# sGPSDO_MCU_1V0.net
KiCad netlist of a schematic drawn in EAGLE
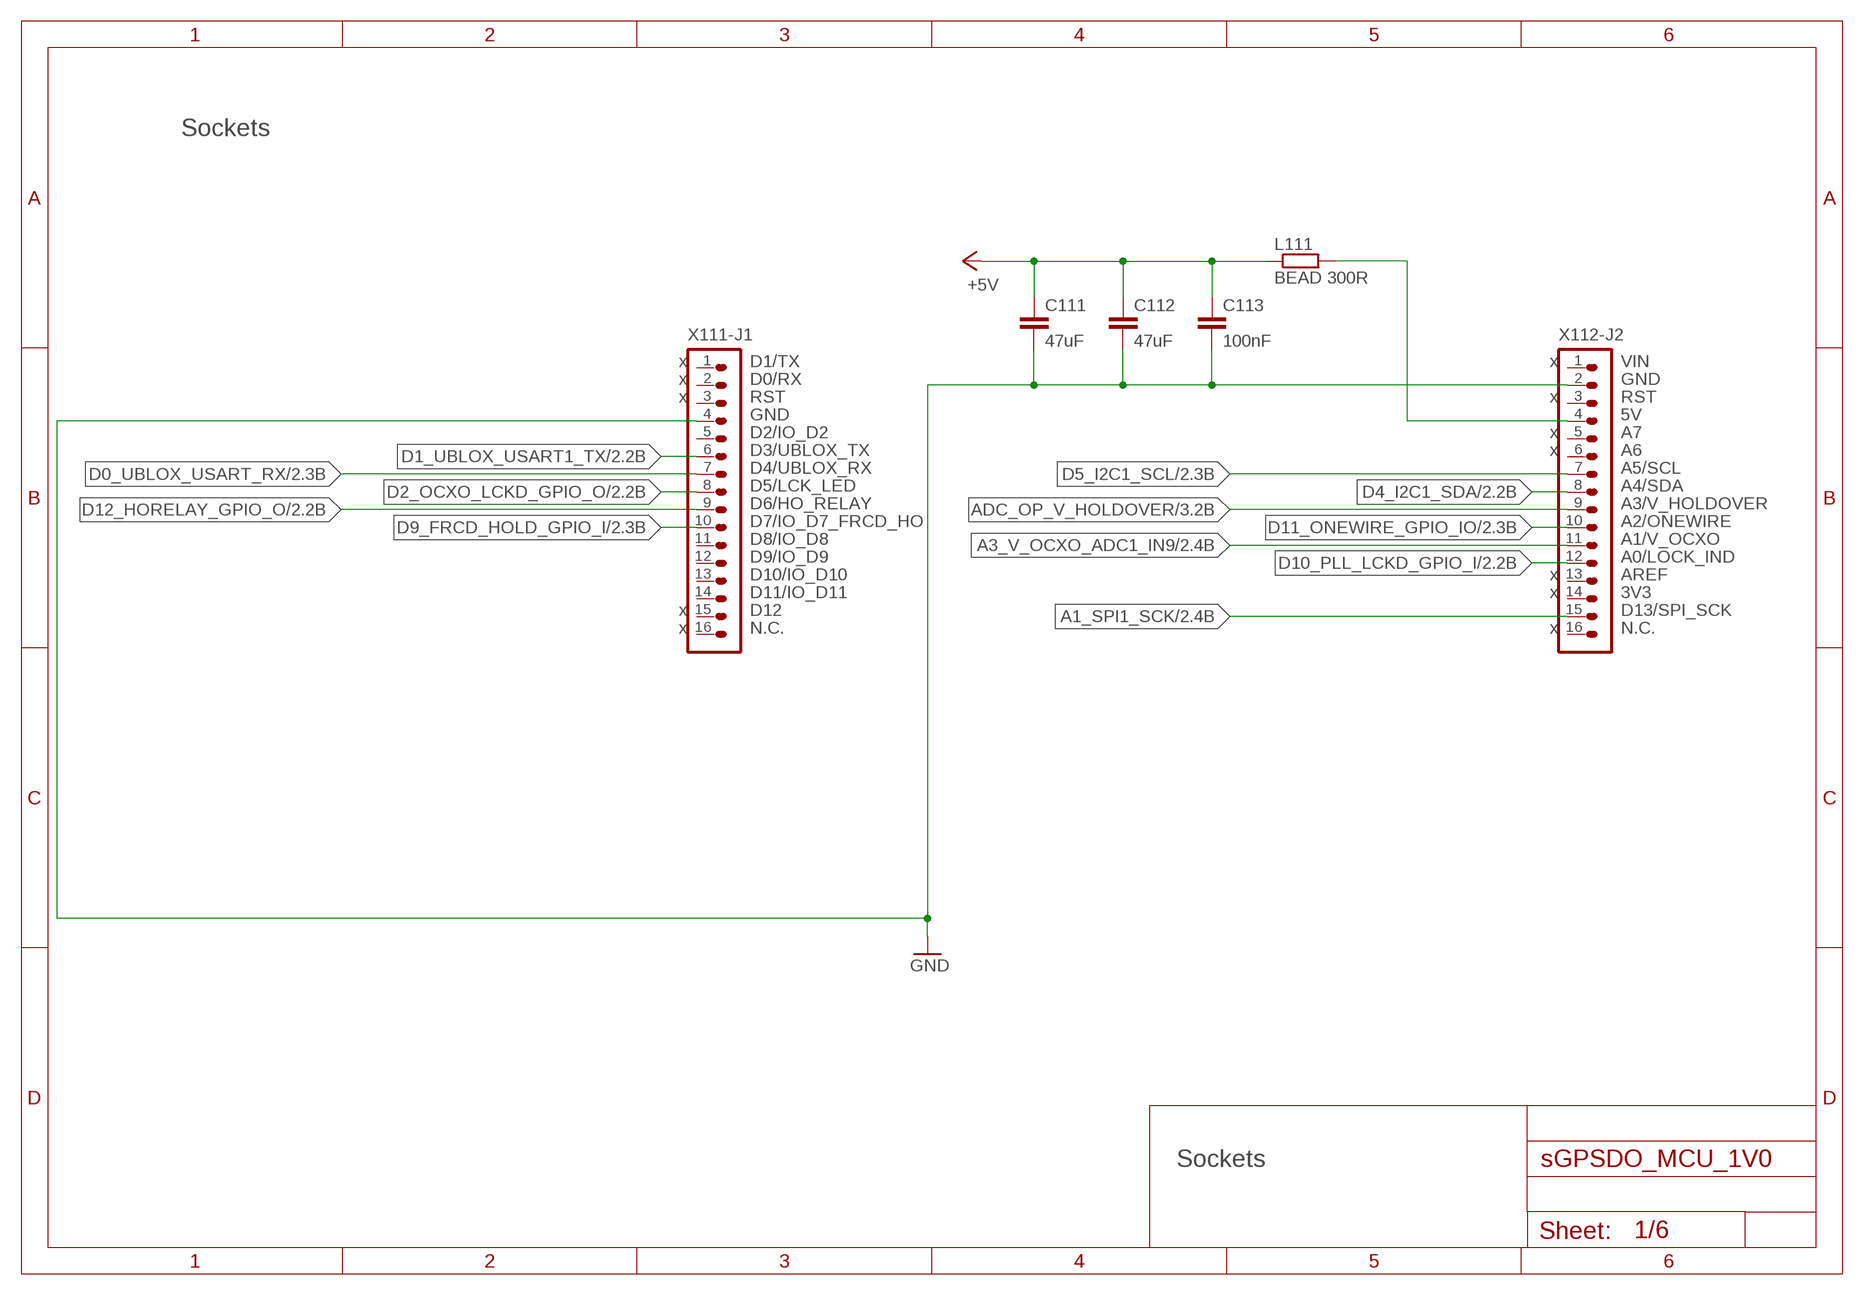
[diagram p0: schematic, sheet 1]
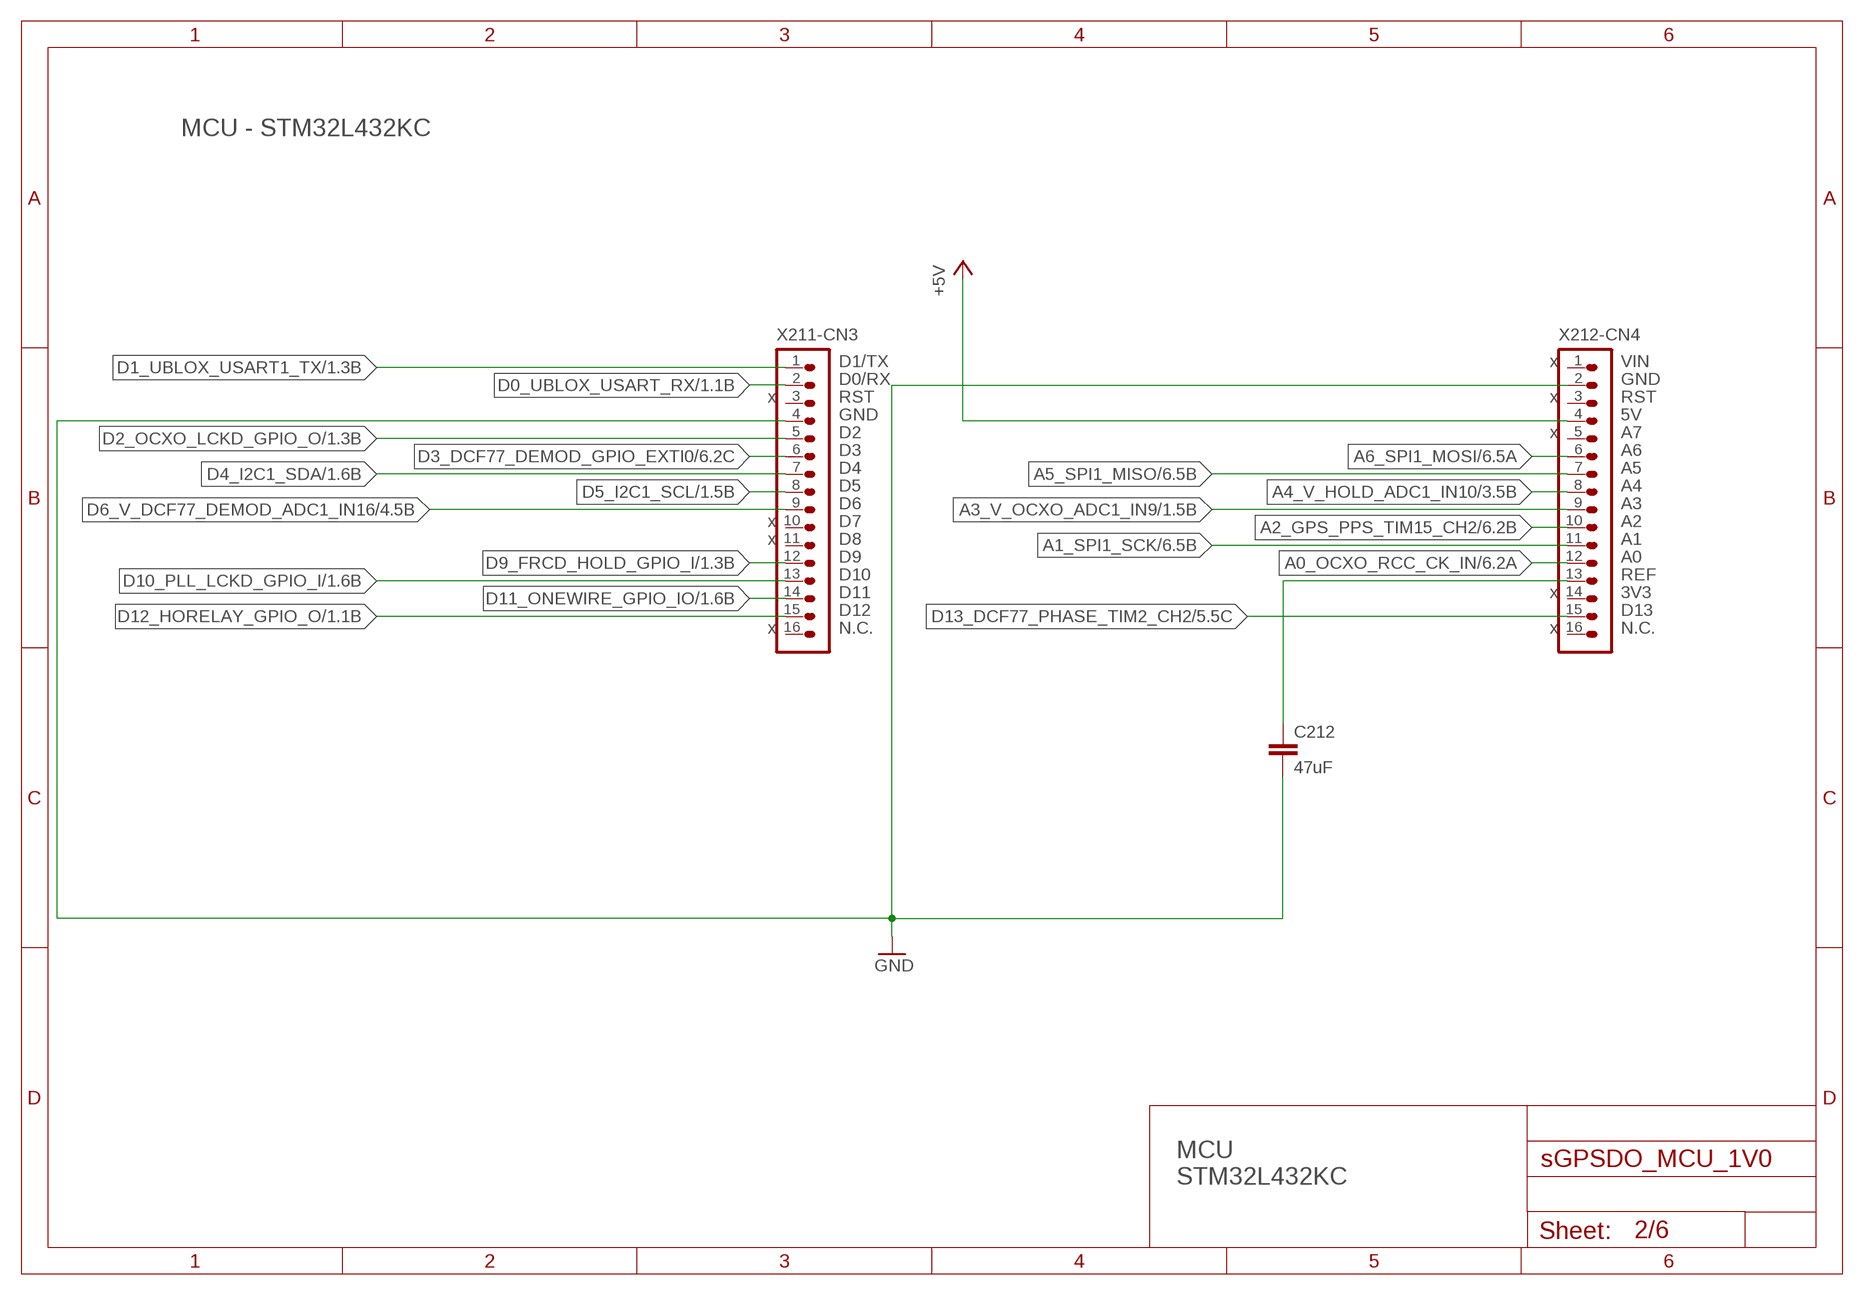
[diagram p1: schematic, sheet 2]
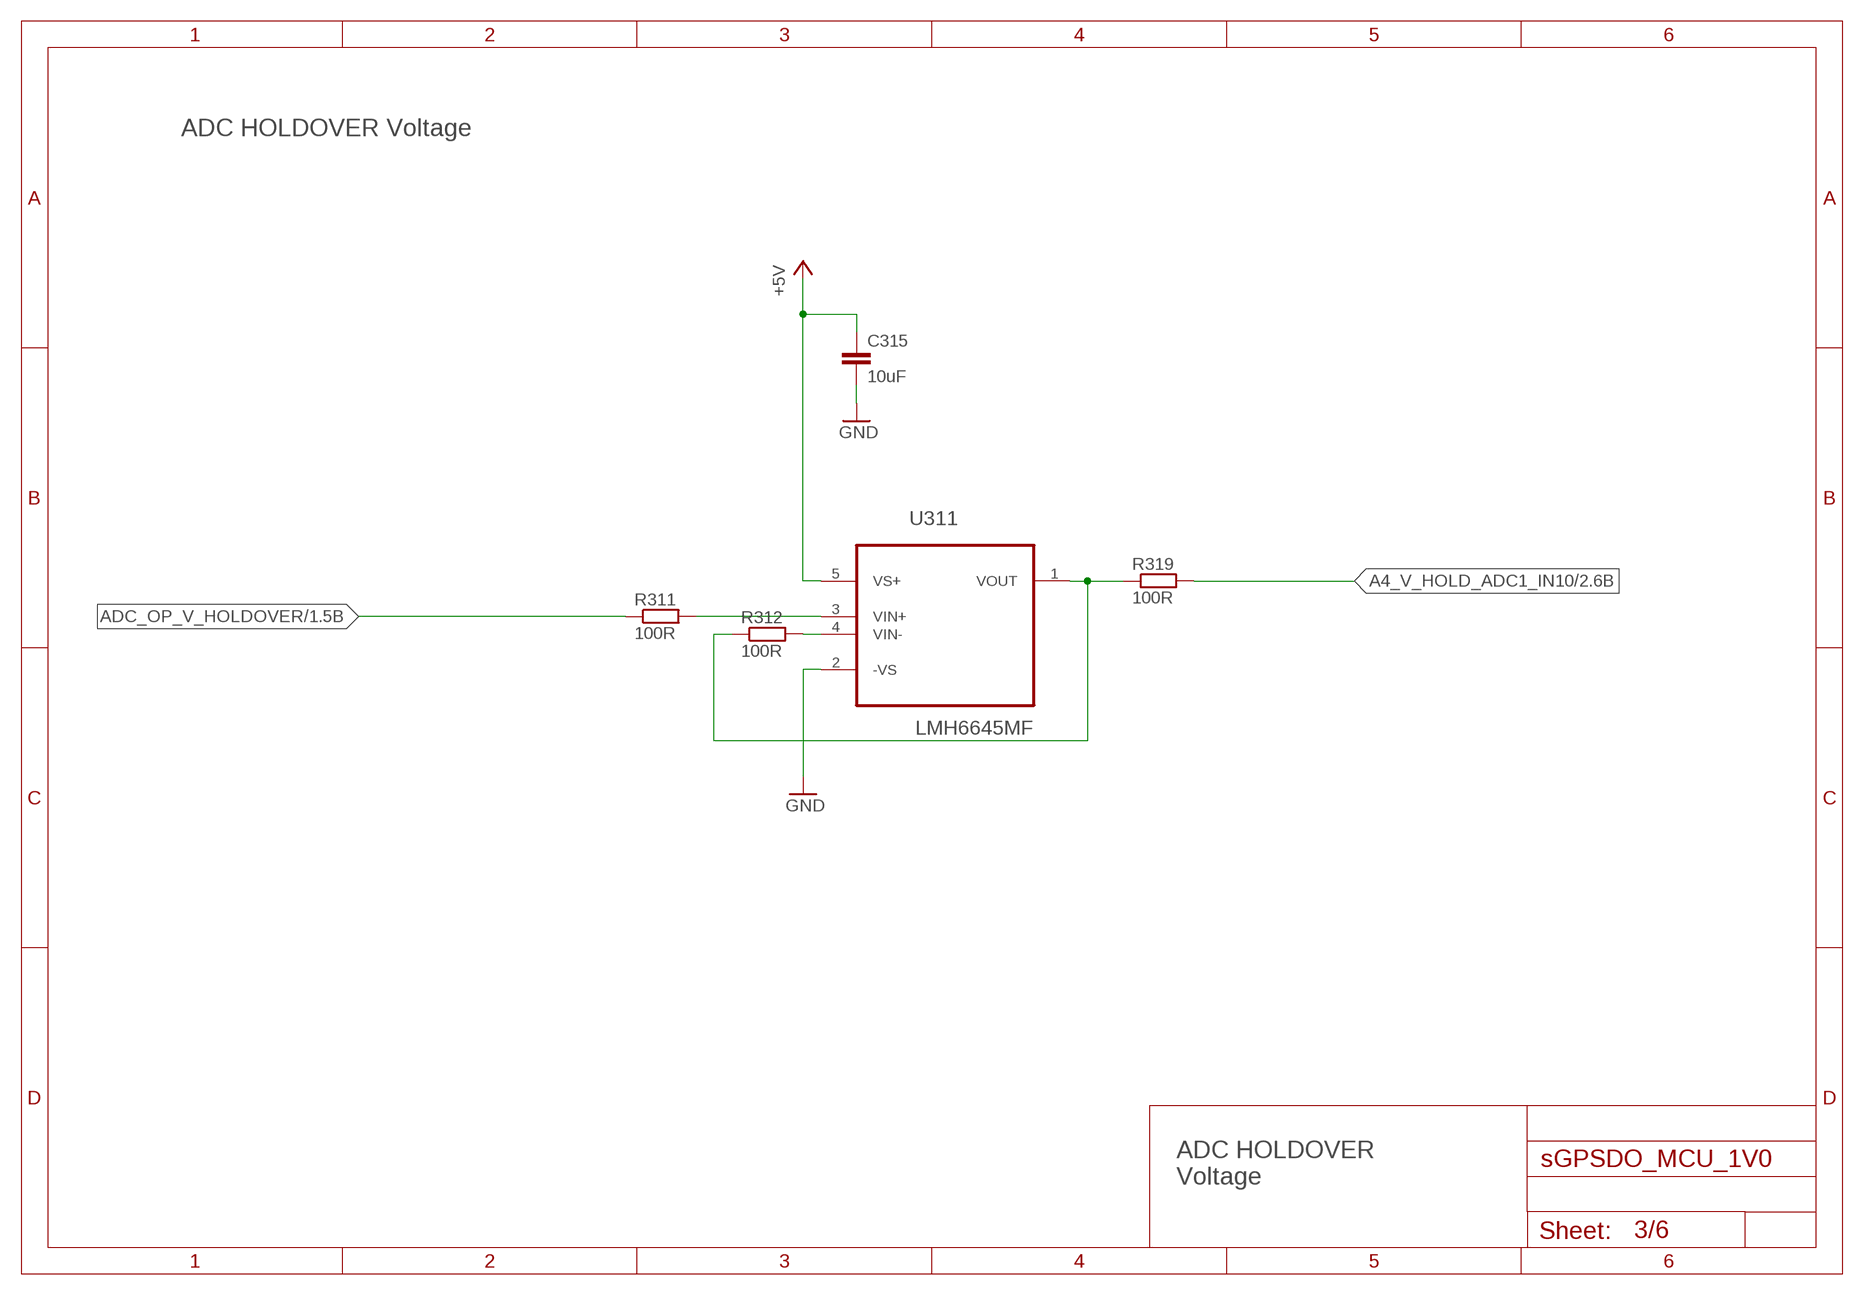
[diagram p2: schematic, sheet 3]
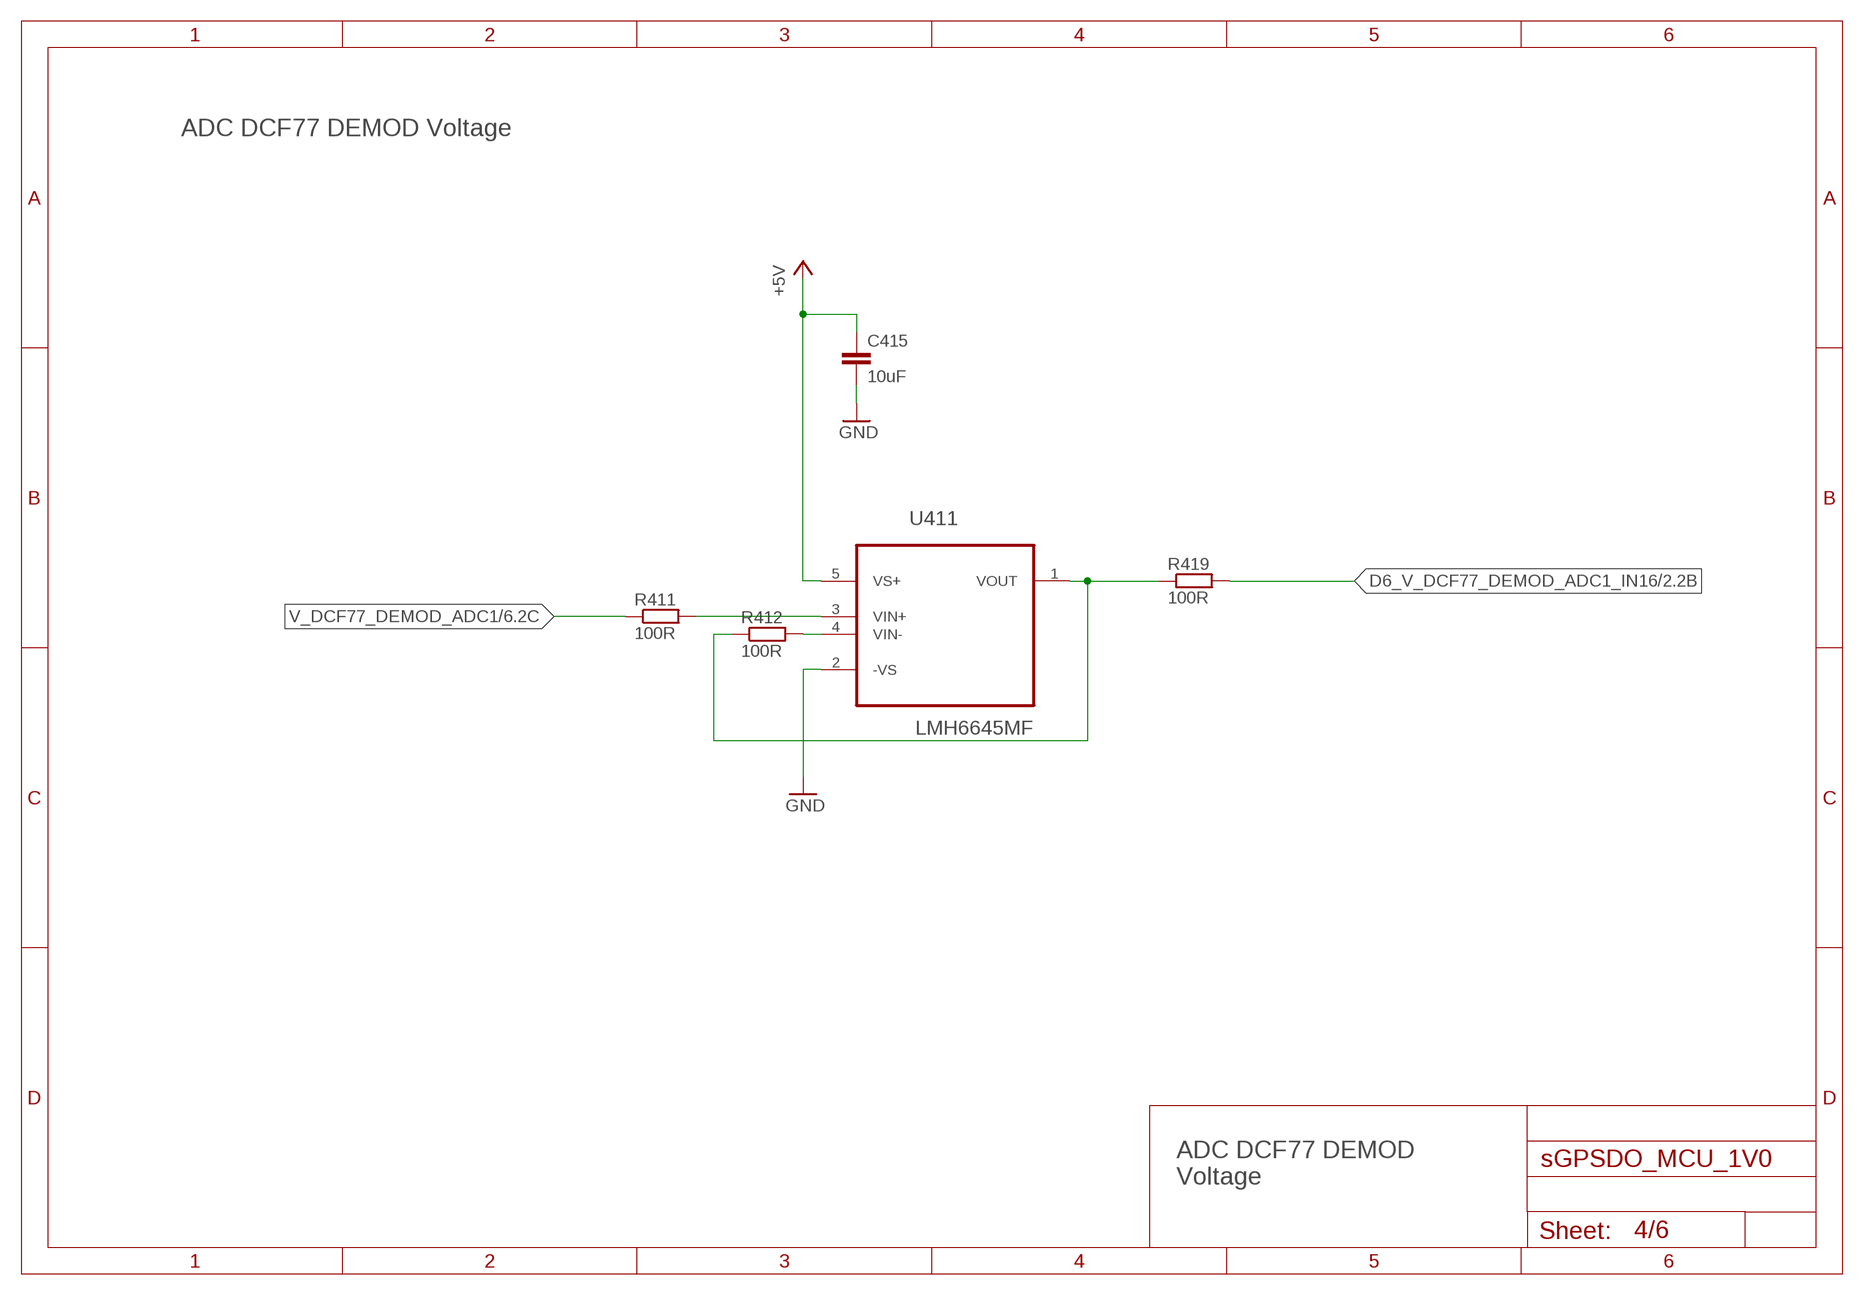
[diagram p3: schematic, sheet 4]
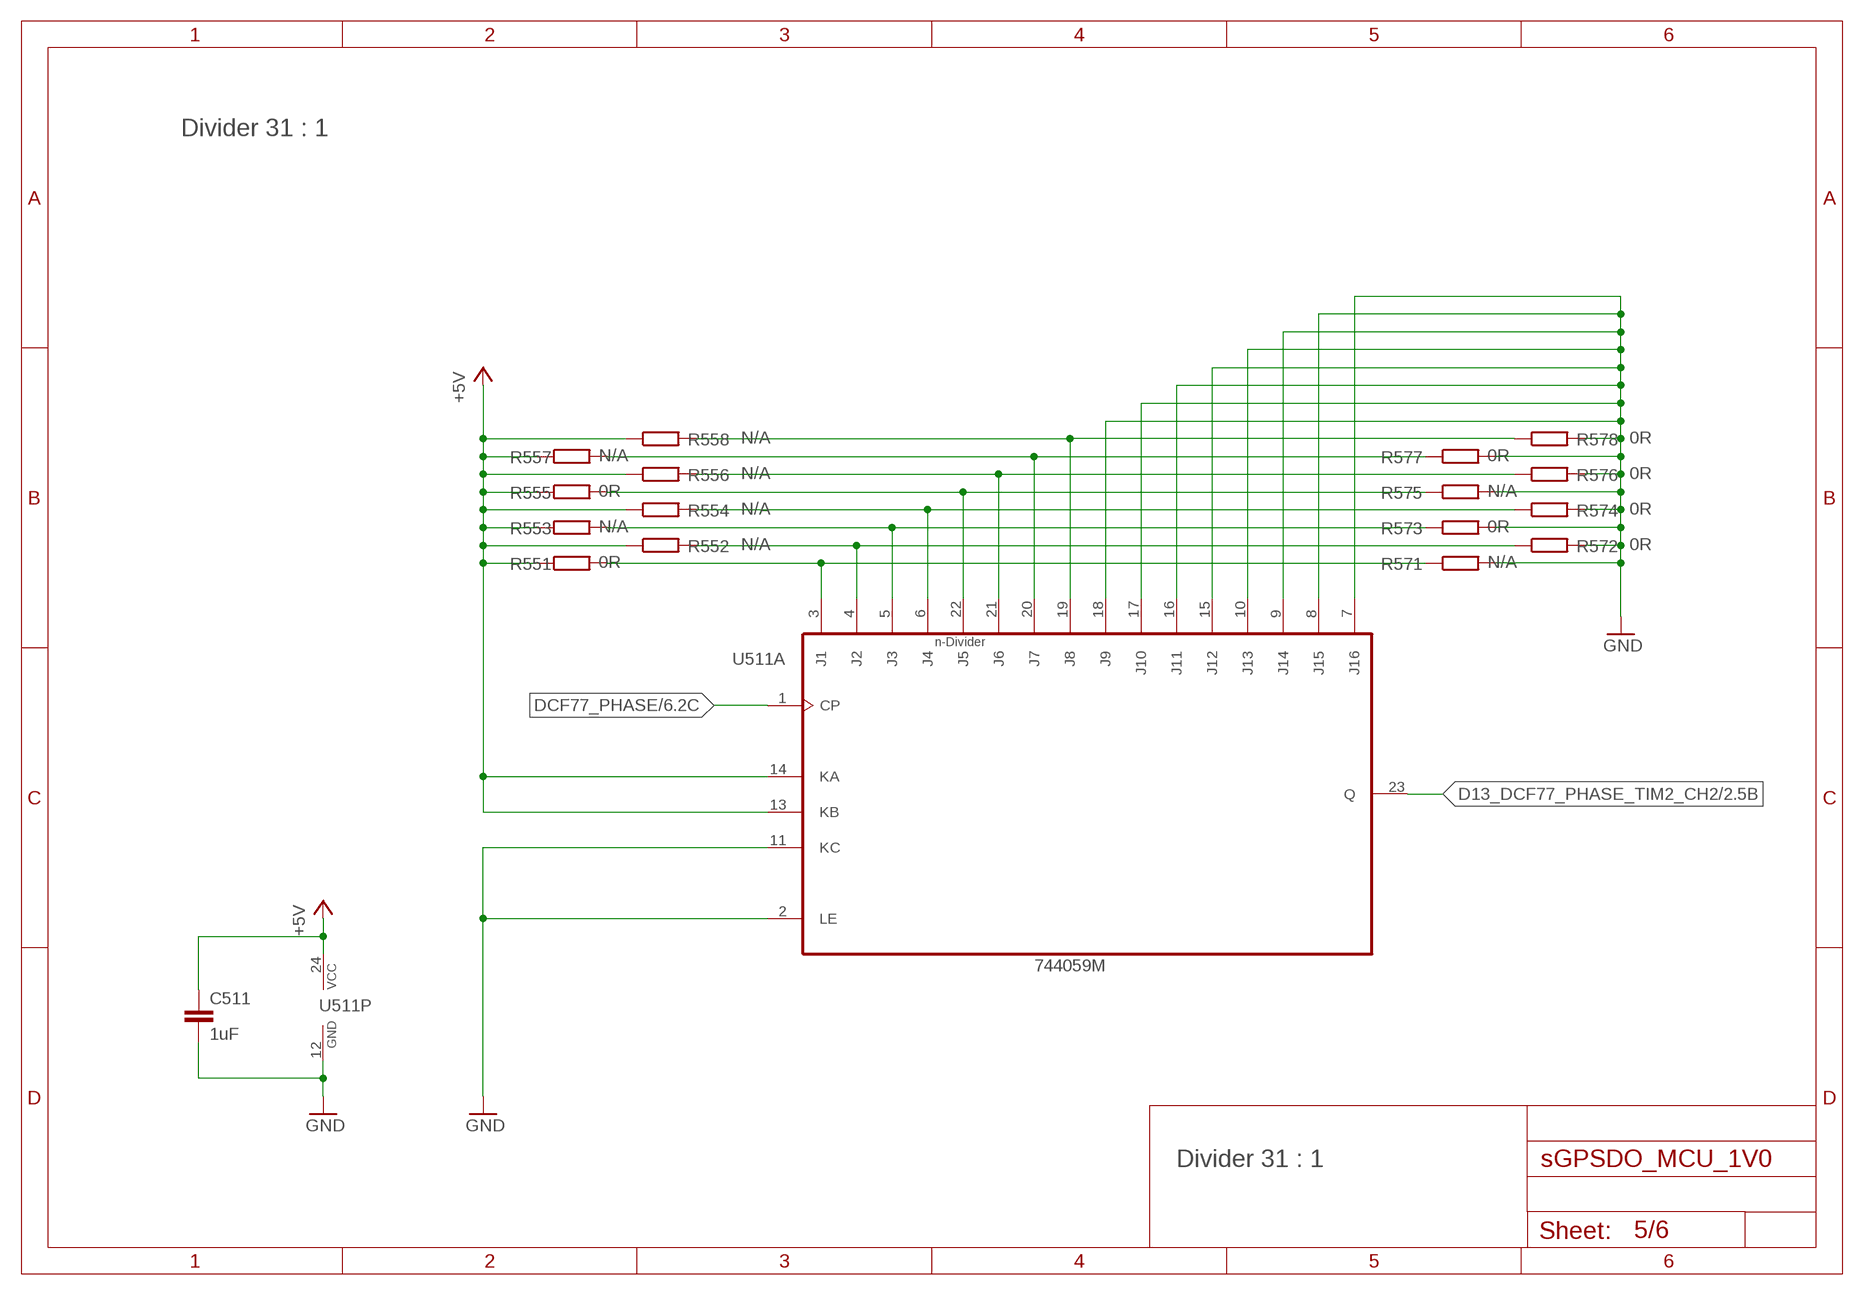
[diagram p4: schematic, sheet 5]
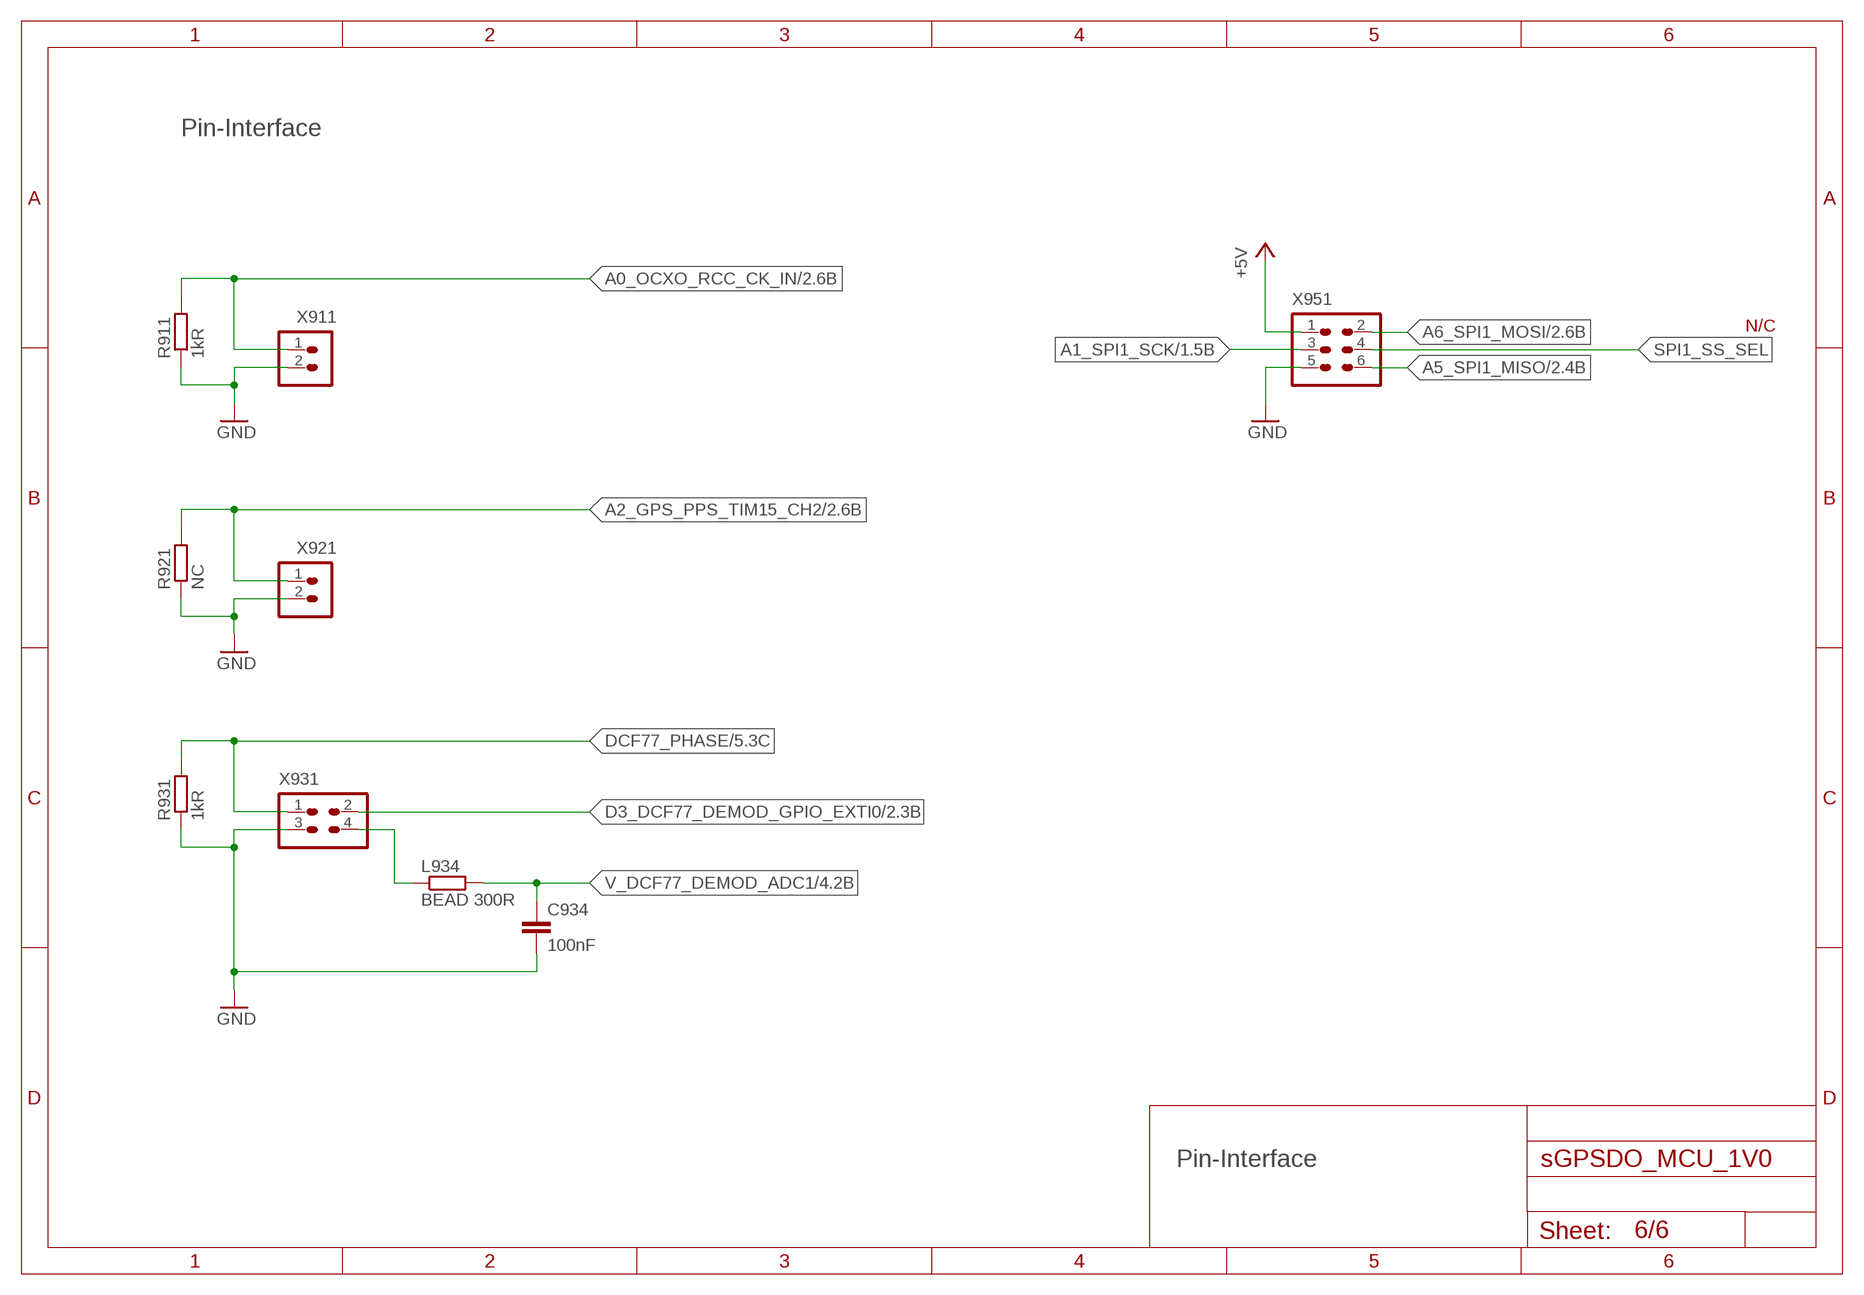
[diagram p5: schematic, sheet 6]

(export (version "E")
  (design (tool "Eeschema 10.0.6"))
  (components
    (comp (ref "C934")
      (value "100nF")
      (footprint "eagle-import:C0805")
      (libsource (lib "eagle-import") (part "C-EUC0805"))
    )
    (comp (ref "L934")
      (value "BEAD 300R")
      (footprint "eagle-import:R1206")
      (libsource (lib "eagle-import") (part "R-EU_R1206"))
    )
    (comp (ref "R911")
      (value "1kR")
      (footprint "eagle-import:R0805")
      (libsource (lib "eagle-import") (part "R-EU_R0805"))
    )
    (comp (ref "R921")
      (value "NC")
      (footprint "eagle-import:R0805")
      (libsource (lib "eagle-import") (part "R-EU_R0805"))
    )
    (comp (ref "R931")
      (value "1kR")
      (footprint "eagle-import:R0805")
      (libsource (lib "eagle-import") (part "R-EU_R0805"))
    )
    (comp (ref "X911")
      (value "HEADER-1X2")
      (footprint "eagle-import:1X02")
      (libsource (lib "eagle-import") (part "HEADER-1X2"))
    )
    (comp (ref "X921")
      (value "HEADER-1X2")
      (footprint "eagle-import:1X02")
      (libsource (lib "eagle-import") (part "HEADER-1X2"))
    )
    (comp (ref "X931")
      (value "HEADER-2X2")
      (footprint "eagle-import:2X02")
      (libsource (lib "eagle-import") (part "HEADER-2X2"))
    )
    (comp (ref "X951")
      (value "HEADER-2X3")
      (footprint "eagle-import:2X03")
      (libsource (lib "eagle-import") (part "HEADER-2X3"))
    )
    (comp (ref "C511")
      (value "1uF")
      (footprint "eagle-import:C0805")
      (libsource (lib "eagle-import") (part "C-EUC0805"))
    )
    (comp (ref "R551")
      (value "0R")
      (footprint "eagle-import:R0402")
      (libsource (lib "eagle-import") (part "R-EU_R0402"))
    )
    (comp (ref "R552")
      (value "N/A")
      (footprint "eagle-import:R0402")
      (libsource (lib "eagle-import") (part "R-EU_R0402"))
    )
    (comp (ref "R553")
      (value "N/A")
      (footprint "eagle-import:R0402")
      (libsource (lib "eagle-import") (part "R-EU_R0402"))
    )
    (comp (ref "R554")
      (value "N/A")
      (footprint "eagle-import:R0402")
      (libsource (lib "eagle-import") (part "R-EU_R0402"))
    )
    (comp (ref "R555")
      (value "0R")
      (footprint "eagle-import:R0402")
      (libsource (lib "eagle-import") (part "R-EU_R0402"))
    )
    (comp (ref "R556")
      (value "N/A")
      (footprint "eagle-import:R0402")
      (libsource (lib "eagle-import") (part "R-EU_R0402"))
    )
    (comp (ref "R557")
      (value "N/A")
      (footprint "eagle-import:R0402")
      (libsource (lib "eagle-import") (part "R-EU_R0402"))
    )
    (comp (ref "R558")
      (value "N/A")
      (footprint "eagle-import:R0402")
      (libsource (lib "eagle-import") (part "R-EU_R0402"))
    )
    (comp (ref "R571")
      (value "N/A")
      (footprint "eagle-import:R0402")
      (libsource (lib "eagle-import") (part "R-EU_R0402"))
    )
    (comp (ref "R572")
      (value "0R")
      (footprint "eagle-import:R0402")
      (libsource (lib "eagle-import") (part "R-EU_R0402"))
    )
    (comp (ref "R573")
      (value "0R")
      (footprint "eagle-import:R0402")
      (libsource (lib "eagle-import") (part "R-EU_R0402"))
    )
    (comp (ref "R574")
      (value "0R")
      (footprint "eagle-import:R0402")
      (libsource (lib "eagle-import") (part "R-EU_R0402"))
    )
    (comp (ref "R575")
      (value "N/A")
      (footprint "eagle-import:R0402")
      (libsource (lib "eagle-import") (part "R-EU_R0402"))
    )
    (comp (ref "R576")
      (value "0R")
      (footprint "eagle-import:R0402")
      (libsource (lib "eagle-import") (part "R-EU_R0402"))
    )
    (comp (ref "R577")
      (value "0R")
      (footprint "eagle-import:R0402")
      (libsource (lib "eagle-import") (part "R-EU_R0402"))
    )
    (comp (ref "R578")
      (value "0R")
      (footprint "eagle-import:R0402")
      (libsource (lib "eagle-import") (part "R-EU_R0402"))
    )
    (comp (ref "U511")
      (value "744059M")
      (footprint "eagle-import:SO24")
      (libsource (lib "eagle-import") (part "744059M"))
    )
    (comp (ref "C415")
      (value "10uF")
      (footprint "eagle-import:C0805")
      (libsource (lib "eagle-import") (part "C-EUC0805"))
    )
    (comp (ref "R411")
      (value "100R")
      (footprint "eagle-import:R0805")
      (libsource (lib "eagle-import") (part "R-EU_R0805"))
    )
    (comp (ref "R412")
      (value "100R")
      (footprint "eagle-import:R0805")
      (libsource (lib "eagle-import") (part "R-EU_R0805"))
    )
    (comp (ref "R419")
      (value "100R")
      (footprint "eagle-import:R0805")
      (libsource (lib "eagle-import") (part "R-EU_R0805"))
    )
    (comp (ref "U411")
      (value "LMH6645MF")
      (footprint "eagle-import:SOT-23-5")
      (libsource (lib "eagle-import") (part "LMH6645MF"))
    )
    (comp (ref "C111")
      (value "47uF")
      (footprint "eagle-import:C0805")
      (libsource (lib "eagle-import") (part "C-EUC0805"))
    )
    (comp (ref "C112")
      (value "47uF")
      (footprint "eagle-import:C0805")
      (libsource (lib "eagle-import") (part "C-EUC0805"))
    )
    (comp (ref "C113")
      (value "100nF")
      (footprint "eagle-import:C0805")
      (libsource (lib "eagle-import") (part "C-EUC0805"))
    )
    (comp (ref "L111")
      (value "BEAD 300R")
      (footprint "eagle-import:R1206")
      (libsource (lib "eagle-import") (part "R-EU_R1206"))
    )
    (comp (ref "X111-J1")
      (value "HEADER-1X16")
      (footprint "eagle-import:1X16")
      (libsource (lib "eagle-import") (part "HEADER-1X16"))
    )
    (comp (ref "X112-J2")
      (value "HEADER-1X16")
      (footprint "eagle-import:1X16")
      (libsource (lib "eagle-import") (part "HEADER-1X16"))
    )
    (comp (ref "C315")
      (value "10uF")
      (footprint "eagle-import:C0805")
      (libsource (lib "eagle-import") (part "C-EUC0805"))
    )
    (comp (ref "R311")
      (value "100R")
      (footprint "eagle-import:R0805")
      (libsource (lib "eagle-import") (part "R-EU_R0805"))
    )
    (comp (ref "R312")
      (value "100R")
      (footprint "eagle-import:R0805")
      (libsource (lib "eagle-import") (part "R-EU_R0805"))
    )
    (comp (ref "R319")
      (value "100R")
      (footprint "eagle-import:R0805")
      (libsource (lib "eagle-import") (part "R-EU_R0805"))
    )
    (comp (ref "U311")
      (value "LMH6645MF")
      (footprint "eagle-import:SOT-23-5")
      (libsource (lib "eagle-import") (part "LMH6645MF"))
    )
    (comp (ref "C212")
      (value "47uF")
      (footprint "eagle-import:C0805")
      (libsource (lib "eagle-import") (part "C-EUC0805"))
    )
    (comp (ref "X211-CN3")
      (value "HEADER-1X16")
      (footprint "eagle-import:1X16")
      (libsource (lib "eagle-import") (part "HEADER-1X16"))
    )
    (comp (ref "X212-CN4")
      (value "HEADER-1X16")
      (footprint "eagle-import:1X16")
      (libsource (lib "eagle-import") (part "HEADER-1X16"))
    )
  )
  (nets
    (net (code "1") (name "+5V") (class "Default")
      (node (ref "C111") (pin "1") (pinfunction "1_1") (pintype "passive"))
      (node (ref "C112") (pin "1") (pinfunction "1_1") (pintype "passive"))
      (node (ref "C113") (pin "1") (pinfunction "1_1") (pintype "passive"))
      (node (ref "C315") (pin "1") (pinfunction "1_1") (pintype "passive"))
      (node (ref "C415") (pin "1") (pinfunction "1_1") (pintype "passive"))
      (node (ref "C511") (pin "1") (pinfunction "1_1") (pintype "passive"))
      (node (ref "L111") (pin "1") (pinfunction "1_1") (pintype "passive"))
      (node (ref "R551") (pin "1") (pinfunction "1_1") (pintype "passive"))
      (node (ref "R552") (pin "1") (pinfunction "1_1") (pintype "passive"))
      (node (ref "R553") (pin "1") (pinfunction "1_1") (pintype "passive"))
      (node (ref "R554") (pin "1") (pinfunction "1_1") (pintype "passive"))
      (node (ref "R555") (pin "1") (pinfunction "1_1") (pintype "passive"))
      (node (ref "R556") (pin "1") (pinfunction "1_1") (pintype "passive"))
      (node (ref "R557") (pin "1") (pinfunction "1_1") (pintype "passive"))
      (node (ref "R558") (pin "1") (pinfunction "1_1") (pintype "passive"))
      (node (ref "U311") (pin "5") (pinfunction "VS+_5") (pintype "power_in"))
      (node (ref "U411") (pin "5") (pinfunction "VS+_5") (pintype "power_in"))
      (node (ref "U511") (pin "13") (pinfunction "KB_13") (pintype "input"))
      (node (ref "U511") (pin "14") (pinfunction "KA_14") (pintype "input"))
      (node (ref "U511") (pin "24") (pinfunction "VCC_24") (pintype "power_in"))
      (node (ref "X212-CN4") (pin "4") (pinfunction "4_4") (pintype "passive"))
      (node (ref "X951") (pin "1") (pinfunction "1_1") (pintype "passive"))
    )
    (net (code "2") (name "A0_OCXO_RCC_CK_IN") (class "Default")
      (node (ref "R911") (pin "2") (pinfunction "2_2") (pintype "passive"))
      (node (ref "X212-CN4") (pin "12") (pinfunction "12_12") (pintype "passive"))
      (node (ref "X911") (pin "1") (pinfunction "1_1") (pintype "passive"))
    )
    (net (code "3") (name "A1_SPI1_SCK") (class "Default")
      (node (ref "X112-J2") (pin "15") (pinfunction "15_15") (pintype "passive"))
      (node (ref "X212-CN4") (pin "11") (pinfunction "11_11") (pintype "passive"))
      (node (ref "X951") (pin "3") (pinfunction "3_3") (pintype "passive"))
    )
    (net (code "4") (name "A2_GPS_PPS_TIM15_CH2") (class "Default")
      (node (ref "R921") (pin "2") (pinfunction "2_2") (pintype "passive"))
      (node (ref "X212-CN4") (pin "10") (pinfunction "10_10") (pintype "passive"))
      (node (ref "X921") (pin "1") (pinfunction "1_1") (pintype "passive"))
    )
    (net (code "5") (name "A3_V_OCXO_ADC1_IN9") (class "Default")
      (node (ref "X112-J2") (pin "11") (pinfunction "11_11") (pintype "passive"))
      (node (ref "X212-CN4") (pin "9") (pinfunction "9_9") (pintype "passive"))
    )
    (net (code "6") (name "A4_V_HOLD_ADC1_IN10") (class "Default")
      (node (ref "R319") (pin "2") (pinfunction "2_2") (pintype "passive"))
      (node (ref "X212-CN4") (pin "8") (pinfunction "8_8") (pintype "passive"))
    )
    (net (code "7") (name "A5_SPI1_MISO") (class "Default")
      (node (ref "X212-CN4") (pin "7") (pinfunction "7_7") (pintype "passive"))
      (node (ref "X951") (pin "6") (pinfunction "6_6") (pintype "passive"))
    )
    (net (code "8") (name "A6_SPI1_MOSI") (class "Default")
      (node (ref "X212-CN4") (pin "6") (pinfunction "6_6") (pintype "passive"))
      (node (ref "X951") (pin "2") (pinfunction "2_2") (pintype "passive"))
    )
    (net (code "9") (name "ADC_OP_V_HOLDOVER") (class "Default")
      (node (ref "R311") (pin "1") (pinfunction "1_1") (pintype "passive"))
      (node (ref "X112-J2") (pin "9") (pinfunction "9_9") (pintype "passive"))
    )
    (net (code "10") (name "D0_UBLOX_USART_RX") (class "Default")
      (node (ref "X111-J1") (pin "7") (pinfunction "7_7") (pintype "passive"))
      (node (ref "X211-CN3") (pin "2") (pinfunction "2_2") (pintype "passive"))
    )
    (net (code "11") (name "D1_UBLOX_USART1_TX") (class "Default")
      (node (ref "X111-J1") (pin "6") (pinfunction "6_6") (pintype "passive"))
      (node (ref "X211-CN3") (pin "1") (pinfunction "1_1") (pintype "passive"))
    )
    (net (code "12") (name "D2_OCXO_LCKD_GPIO_O") (class "Default")
      (node (ref "X111-J1") (pin "8") (pinfunction "8_8") (pintype "passive"))
      (node (ref "X211-CN3") (pin "5") (pinfunction "5_5") (pintype "passive"))
    )
    (net (code "13") (name "D3_DCF77_DEMOD_GPIO_EXTI0") (class "Default")
      (node (ref "X211-CN3") (pin "6") (pinfunction "6_6") (pintype "passive"))
      (node (ref "X931") (pin "2") (pinfunction "2_2") (pintype "passive"))
    )
    (net (code "14") (name "D4_I2C1_SDA") (class "Default")
      (node (ref "X112-J2") (pin "8") (pinfunction "8_8") (pintype "passive"))
      (node (ref "X211-CN3") (pin "7") (pinfunction "7_7") (pintype "passive"))
    )
    (net (code "15") (name "D5_I2C1_SCL") (class "Default")
      (node (ref "X112-J2") (pin "7") (pinfunction "7_7") (pintype "passive"))
      (node (ref "X211-CN3") (pin "8") (pinfunction "8_8") (pintype "passive"))
    )
    (net (code "16") (name "D6_V_DCF77_DEMOD_ADC1_IN16") (class "Default")
      (node (ref "R419") (pin "2") (pinfunction "2_2") (pintype "passive"))
      (node (ref "X211-CN3") (pin "9") (pinfunction "9_9") (pintype "passive"))
    )
    (net (code "17") (name "D9_FRCD_HOLD_GPIO_I") (class "Default")
      (node (ref "X111-J1") (pin "10") (pinfunction "10_10") (pintype "passive"))
      (node (ref "X211-CN3") (pin "12") (pinfunction "12_12") (pintype "passive"))
    )
    (net (code "18") (name "D10_PLL_LCKD_GPIO_I") (class "Default")
      (node (ref "X112-J2") (pin "12") (pinfunction "12_12") (pintype "passive"))
      (node (ref "X211-CN3") (pin "13") (pinfunction "13_13") (pintype "passive"))
    )
    (net (code "19") (name "D11_ONEWIRE_GPIO_IO") (class "Default")
      (node (ref "X112-J2") (pin "10") (pinfunction "10_10") (pintype "passive"))
      (node (ref "X211-CN3") (pin "14") (pinfunction "14_14") (pintype "passive"))
    )
    (net (code "20") (name "D12_HORELAY_GPIO_O") (class "Default")
      (node (ref "X111-J1") (pin "9") (pinfunction "9_9") (pintype "passive"))
      (node (ref "X211-CN3") (pin "15") (pinfunction "15_15") (pintype "passive"))
    )
    (net (code "21") (name "D13_DCF77_PHASE_TIM2_CH2") (class "Default")
      (node (ref "U511") (pin "23") (pinfunction "Q_23") (pintype "output"))
      (node (ref "X212-CN4") (pin "15") (pinfunction "15_15") (pintype "passive"))
    )
    (net (code "22") (name "DCF77_PHASE") (class "Default")
      (node (ref "R931") (pin "2") (pinfunction "2_2") (pintype "passive"))
      (node (ref "U511") (pin "1") (pinfunction "CP_1") (pintype "input"))
      (node (ref "X931") (pin "1") (pinfunction "1_1") (pintype "passive"))
    )
    (net (code "23") (name "GND") (class "Default")
      (node (ref "C111") (pin "2") (pinfunction "2_2") (pintype "passive"))
      (node (ref "C112") (pin "2") (pinfunction "2_2") (pintype "passive"))
      (node (ref "C113") (pin "2") (pinfunction "2_2") (pintype "passive"))
      (node (ref "C212") (pin "2") (pinfunction "2_2") (pintype "passive"))
      (node (ref "C315") (pin "2") (pinfunction "2_2") (pintype "passive"))
      (node (ref "C415") (pin "2") (pinfunction "2_2") (pintype "passive"))
      (node (ref "C511") (pin "2") (pinfunction "2_2") (pintype "passive"))
      (node (ref "C934") (pin "2") (pinfunction "2_2") (pintype "passive"))
      (node (ref "R571") (pin "2") (pinfunction "2_2") (pintype "passive"))
      (node (ref "R572") (pin "2") (pinfunction "2_2") (pintype "passive"))
      (node (ref "R573") (pin "2") (pinfunction "2_2") (pintype "passive"))
      (node (ref "R574") (pin "2") (pinfunction "2_2") (pintype "passive"))
      (node (ref "R575") (pin "2") (pinfunction "2_2") (pintype "passive"))
      (node (ref "R576") (pin "2") (pinfunction "2_2") (pintype "passive"))
      (node (ref "R577") (pin "2") (pinfunction "2_2") (pintype "passive"))
      (node (ref "R578") (pin "2") (pinfunction "2_2") (pintype "passive"))
      (node (ref "R911") (pin "1") (pinfunction "1_1") (pintype "passive"))
      (node (ref "R921") (pin "1") (pinfunction "1_1") (pintype "passive"))
      (node (ref "R931") (pin "1") (pinfunction "1_1") (pintype "passive"))
      (node (ref "U311") (pin "2") (pinfunction "-VS_2") (pintype "power_in"))
      (node (ref "U411") (pin "2") (pinfunction "-VS_2") (pintype "power_in"))
      (node (ref "U511") (pin "10") (pinfunction "J13_10") (pintype "input"))
      (node (ref "U511") (pin "11") (pinfunction "KC_11") (pintype "input"))
      (node (ref "U511") (pin "12") (pinfunction "GND_12") (pintype "power_in"))
      (node (ref "U511") (pin "15") (pinfunction "J12_15") (pintype "input"))
      (node (ref "U511") (pin "16") (pinfunction "J11_16") (pintype "input"))
      (node (ref "U511") (pin "17") (pinfunction "J10_17") (pintype "input"))
      (node (ref "U511") (pin "18") (pinfunction "J9_18") (pintype "input"))
      (node (ref "U511") (pin "2") (pinfunction "LE_2") (pintype "input"))
      (node (ref "U511") (pin "7") (pinfunction "J16_7") (pintype "input"))
      (node (ref "U511") (pin "8") (pinfunction "J15_8") (pintype "input"))
      (node (ref "U511") (pin "9") (pinfunction "J14_9") (pintype "input"))
      (node (ref "X111-J1") (pin "4") (pinfunction "4_4") (pintype "passive"))
      (node (ref "X112-J2") (pin "2") (pinfunction "2_2") (pintype "passive"))
      (node (ref "X211-CN3") (pin "4") (pinfunction "4_4") (pintype "passive"))
      (node (ref "X212-CN4") (pin "2") (pinfunction "2_2") (pintype "passive"))
      (node (ref "X911") (pin "2") (pinfunction "2_2") (pintype "passive"))
      (node (ref "X921") (pin "2") (pinfunction "2_2") (pintype "passive"))
      (node (ref "X931") (pin "3") (pinfunction "3_3") (pintype "passive"))
      (node (ref "X951") (pin "5") (pinfunction "5_5") (pintype "passive"))
    )
    (net (code "24") (name "Net-(C212-Pad1)") (class "Default")
      (node (ref "C212") (pin "1") (pinfunction "1_1") (pintype "passive"))
      (node (ref "X212-CN4") (pin "13") (pinfunction "13_13") (pintype "passive"))
    )
    (net (code "25") (name "Net-(L111-Pad2)") (class "Default")
      (node (ref "L111") (pin "2") (pinfunction "2_2") (pintype "passive"))
      (node (ref "X112-J2") (pin "4") (pinfunction "4_4") (pintype "passive"))
    )
    (net (code "26") (name "Net-(L934-Pad1)") (class "Default")
      (node (ref "L934") (pin "1") (pinfunction "1_1") (pintype "passive"))
      (node (ref "X931") (pin "4") (pinfunction "4_4") (pintype "passive"))
    )
    (net (code "27") (name "Net-(U311-VIN+)") (class "Default")
      (node (ref "R311") (pin "2") (pinfunction "2_2") (pintype "passive"))
      (node (ref "U311") (pin "3") (pinfunction "VIN+_3") (pintype "input"))
    )
    (net (code "28") (name "Net-(U311-VIN-)") (class "Default")
      (node (ref "R312") (pin "2") (pinfunction "2_2") (pintype "passive"))
      (node (ref "U311") (pin "4") (pinfunction "VIN-_4") (pintype "input"))
    )
    (net (code "29") (name "Net-(U311-VOUT)") (class "Default")
      (node (ref "R312") (pin "1") (pinfunction "1_1") (pintype "passive"))
      (node (ref "R319") (pin "1") (pinfunction "1_1") (pintype "passive"))
      (node (ref "U311") (pin "1") (pinfunction "VOUT_1") (pintype "output"))
    )
    (net (code "30") (name "Net-(U411-VIN+)") (class "Default")
      (node (ref "R411") (pin "2") (pinfunction "2_2") (pintype "passive"))
      (node (ref "U411") (pin "3") (pinfunction "VIN+_3") (pintype "input"))
    )
    (net (code "31") (name "Net-(U411-VIN-)") (class "Default")
      (node (ref "R412") (pin "2") (pinfunction "2_2") (pintype "passive"))
      (node (ref "U411") (pin "4") (pinfunction "VIN-_4") (pintype "input"))
    )
    (net (code "32") (name "Net-(U411-VOUT)") (class "Default")
      (node (ref "R412") (pin "1") (pinfunction "1_1") (pintype "passive"))
      (node (ref "R419") (pin "1") (pinfunction "1_1") (pintype "passive"))
      (node (ref "U411") (pin "1") (pinfunction "VOUT_1") (pintype "output"))
    )
    (net (code "33") (name "Net-(U511A-J1)") (class "Default")
      (node (ref "R551") (pin "2") (pinfunction "2_2") (pintype "passive"))
      (node (ref "R571") (pin "1") (pinfunction "1_1") (pintype "passive"))
      (node (ref "U511") (pin "3") (pinfunction "J1_3") (pintype "input"))
    )
    (net (code "34") (name "Net-(U511A-J2)") (class "Default")
      (node (ref "R552") (pin "2") (pinfunction "2_2") (pintype "passive"))
      (node (ref "R572") (pin "1") (pinfunction "1_1") (pintype "passive"))
      (node (ref "U511") (pin "4") (pinfunction "J2_4") (pintype "input"))
    )
    (net (code "35") (name "Net-(U511A-J3)") (class "Default")
      (node (ref "R553") (pin "2") (pinfunction "2_2") (pintype "passive"))
      (node (ref "R573") (pin "1") (pinfunction "1_1") (pintype "passive"))
      (node (ref "U511") (pin "5") (pinfunction "J3_5") (pintype "input"))
    )
    (net (code "36") (name "Net-(U511A-J4)") (class "Default")
      (node (ref "R554") (pin "2") (pinfunction "2_2") (pintype "passive"))
      (node (ref "R574") (pin "1") (pinfunction "1_1") (pintype "passive"))
      (node (ref "U511") (pin "6") (pinfunction "J4_6") (pintype "input"))
    )
    (net (code "37") (name "Net-(U511A-J5)") (class "Default")
      (node (ref "R555") (pin "2") (pinfunction "2_2") (pintype "passive"))
      (node (ref "R575") (pin "1") (pinfunction "1_1") (pintype "passive"))
      (node (ref "U511") (pin "22") (pinfunction "J5_22") (pintype "input"))
    )
    (net (code "38") (name "Net-(U511A-J6)") (class "Default")
      (node (ref "R556") (pin "2") (pinfunction "2_2") (pintype "passive"))
      (node (ref "R576") (pin "1") (pinfunction "1_1") (pintype "passive"))
      (node (ref "U511") (pin "21") (pinfunction "J6_21") (pintype "input"))
    )
    (net (code "39") (name "Net-(U511A-J7)") (class "Default")
      (node (ref "R557") (pin "2") (pinfunction "2_2") (pintype "passive"))
      (node (ref "R577") (pin "1") (pinfunction "1_1") (pintype "passive"))
      (node (ref "U511") (pin "20") (pinfunction "J7_20") (pintype "input"))
    )
    (net (code "40") (name "Net-(U511A-J8)") (class "Default")
      (node (ref "R558") (pin "2") (pinfunction "2_2") (pintype "passive"))
      (node (ref "R578") (pin "1") (pinfunction "1_1") (pintype "passive"))
      (node (ref "U511") (pin "19") (pinfunction "J8_19") (pintype "input"))
    )
    (net (code "41") (name "SPI1_SS_SEL") (class "Default")
      (node (ref "X951") (pin "4") (pinfunction "4_4") (pintype "passive"))
    )
    (net (code "42") (name "V_DCF77_DEMOD_ADC1") (class "Default")
      (node (ref "C934") (pin "1") (pinfunction "1_1") (pintype "passive"))
      (node (ref "L934") (pin "2") (pinfunction "2_2") (pintype "passive"))
      (node (ref "R411") (pin "1") (pinfunction "1_1") (pintype "passive"))
    )
    (net (code "43") (name "unconnected-(X111-J1-Pad1)") (class "Default")
      (node (ref "X111-J1") (pin "1") (pinfunction "1_1") (pintype "passive"))
    )
    (net (code "44") (name "unconnected-(X111-J1-Pad2)") (class "Default")
      (node (ref "X111-J1") (pin "2") (pinfunction "2_2") (pintype "passive"))
    )
    (net (code "45") (name "unconnected-(X111-J1-Pad3)") (class "Default")
      (node (ref "X111-J1") (pin "3") (pinfunction "3_3") (pintype "passive"))
    )
    (net (code "46") (name "unconnected-(X111-J1-Pad5)") (class "Default")
      (node (ref "X111-J1") (pin "5") (pinfunction "5_5") (pintype "passive"))
    )
    (net (code "47") (name "unconnected-(X111-J1-Pad11)") (class "Default")
      (node (ref "X111-J1") (pin "11") (pinfunction "11_11") (pintype "passive"))
    )
    (net (code "48") (name "unconnected-(X111-J1-Pad12)") (class "Default")
      (node (ref "X111-J1") (pin "12") (pinfunction "12_12") (pintype "passive"))
    )
    (net (code "49") (name "unconnected-(X111-J1-Pad13)") (class "Default")
      (node (ref "X111-J1") (pin "13") (pinfunction "13_13") (pintype "passive"))
    )
    (net (code "50") (name "unconnected-(X111-J1-Pad14)") (class "Default")
      (node (ref "X111-J1") (pin "14") (pinfunction "14_14") (pintype "passive"))
    )
    (net (code "51") (name "unconnected-(X111-J1-Pad15)") (class "Default")
      (node (ref "X111-J1") (pin "15") (pinfunction "15_15") (pintype "passive"))
    )
    (net (code "52") (name "unconnected-(X111-J1-Pad16)") (class "Default")
      (node (ref "X111-J1") (pin "16") (pinfunction "16_16") (pintype "passive"))
    )
    (net (code "53") (name "unconnected-(X112-J2-Pad1)") (class "Default")
      (node (ref "X112-J2") (pin "1") (pinfunction "1_1") (pintype "passive"))
    )
    (net (code "54") (name "unconnected-(X112-J2-Pad3)") (class "Default")
      (node (ref "X112-J2") (pin "3") (pinfunction "3_3") (pintype "passive"))
    )
    (net (code "55") (name "unconnected-(X112-J2-Pad5)") (class "Default")
      (node (ref "X112-J2") (pin "5") (pinfunction "5_5") (pintype "passive"))
    )
    (net (code "56") (name "unconnected-(X112-J2-Pad6)") (class "Default")
      (node (ref "X112-J2") (pin "6") (pinfunction "6_6") (pintype "passive"))
    )
    (net (code "57") (name "unconnected-(X112-J2-Pad13)") (class "Default")
      (node (ref "X112-J2") (pin "13") (pinfunction "13_13") (pintype "passive"))
    )
    (net (code "58") (name "unconnected-(X112-J2-Pad14)") (class "Default")
      (node (ref "X112-J2") (pin "14") (pinfunction "14_14") (pintype "passive"))
    )
    (net (code "59") (name "unconnected-(X112-J2-Pad16)") (class "Default")
      (node (ref "X112-J2") (pin "16") (pinfunction "16_16") (pintype "passive"))
    )
    (net (code "60") (name "unconnected-(X211-CN3-Pad3)") (class "Default")
      (node (ref "X211-CN3") (pin "3") (pinfunction "3_3") (pintype "passive"))
    )
    (net (code "61") (name "unconnected-(X211-CN3-Pad10)") (class "Default")
      (node (ref "X211-CN3") (pin "10") (pinfunction "10_10") (pintype "passive"))
    )
    (net (code "62") (name "unconnected-(X211-CN3-Pad11)") (class "Default")
      (node (ref "X211-CN3") (pin "11") (pinfunction "11_11") (pintype "passive"))
    )
    (net (code "63") (name "unconnected-(X211-CN3-Pad16)") (class "Default")
      (node (ref "X211-CN3") (pin "16") (pinfunction "16_16") (pintype "passive"))
    )
    (net (code "64") (name "unconnected-(X212-CN4-Pad1)") (class "Default")
      (node (ref "X212-CN4") (pin "1") (pinfunction "1_1") (pintype "passive"))
    )
    (net (code "65") (name "unconnected-(X212-CN4-Pad3)") (class "Default")
      (node (ref "X212-CN4") (pin "3") (pinfunction "3_3") (pintype "passive"))
    )
    (net (code "66") (name "unconnected-(X212-CN4-Pad5)") (class "Default")
      (node (ref "X212-CN4") (pin "5") (pinfunction "5_5") (pintype "passive"))
    )
    (net (code "67") (name "unconnected-(X212-CN4-Pad14)") (class "Default")
      (node (ref "X212-CN4") (pin "14") (pinfunction "14_14") (pintype "passive"))
    )
    (net (code "68") (name "unconnected-(X212-CN4-Pad16)") (class "Default")
      (node (ref "X212-CN4") (pin "16") (pinfunction "16_16") (pintype "passive"))
    )
  )
)
